# MiniBee.net
KiCad netlist of a schematic drawn in EAGLE
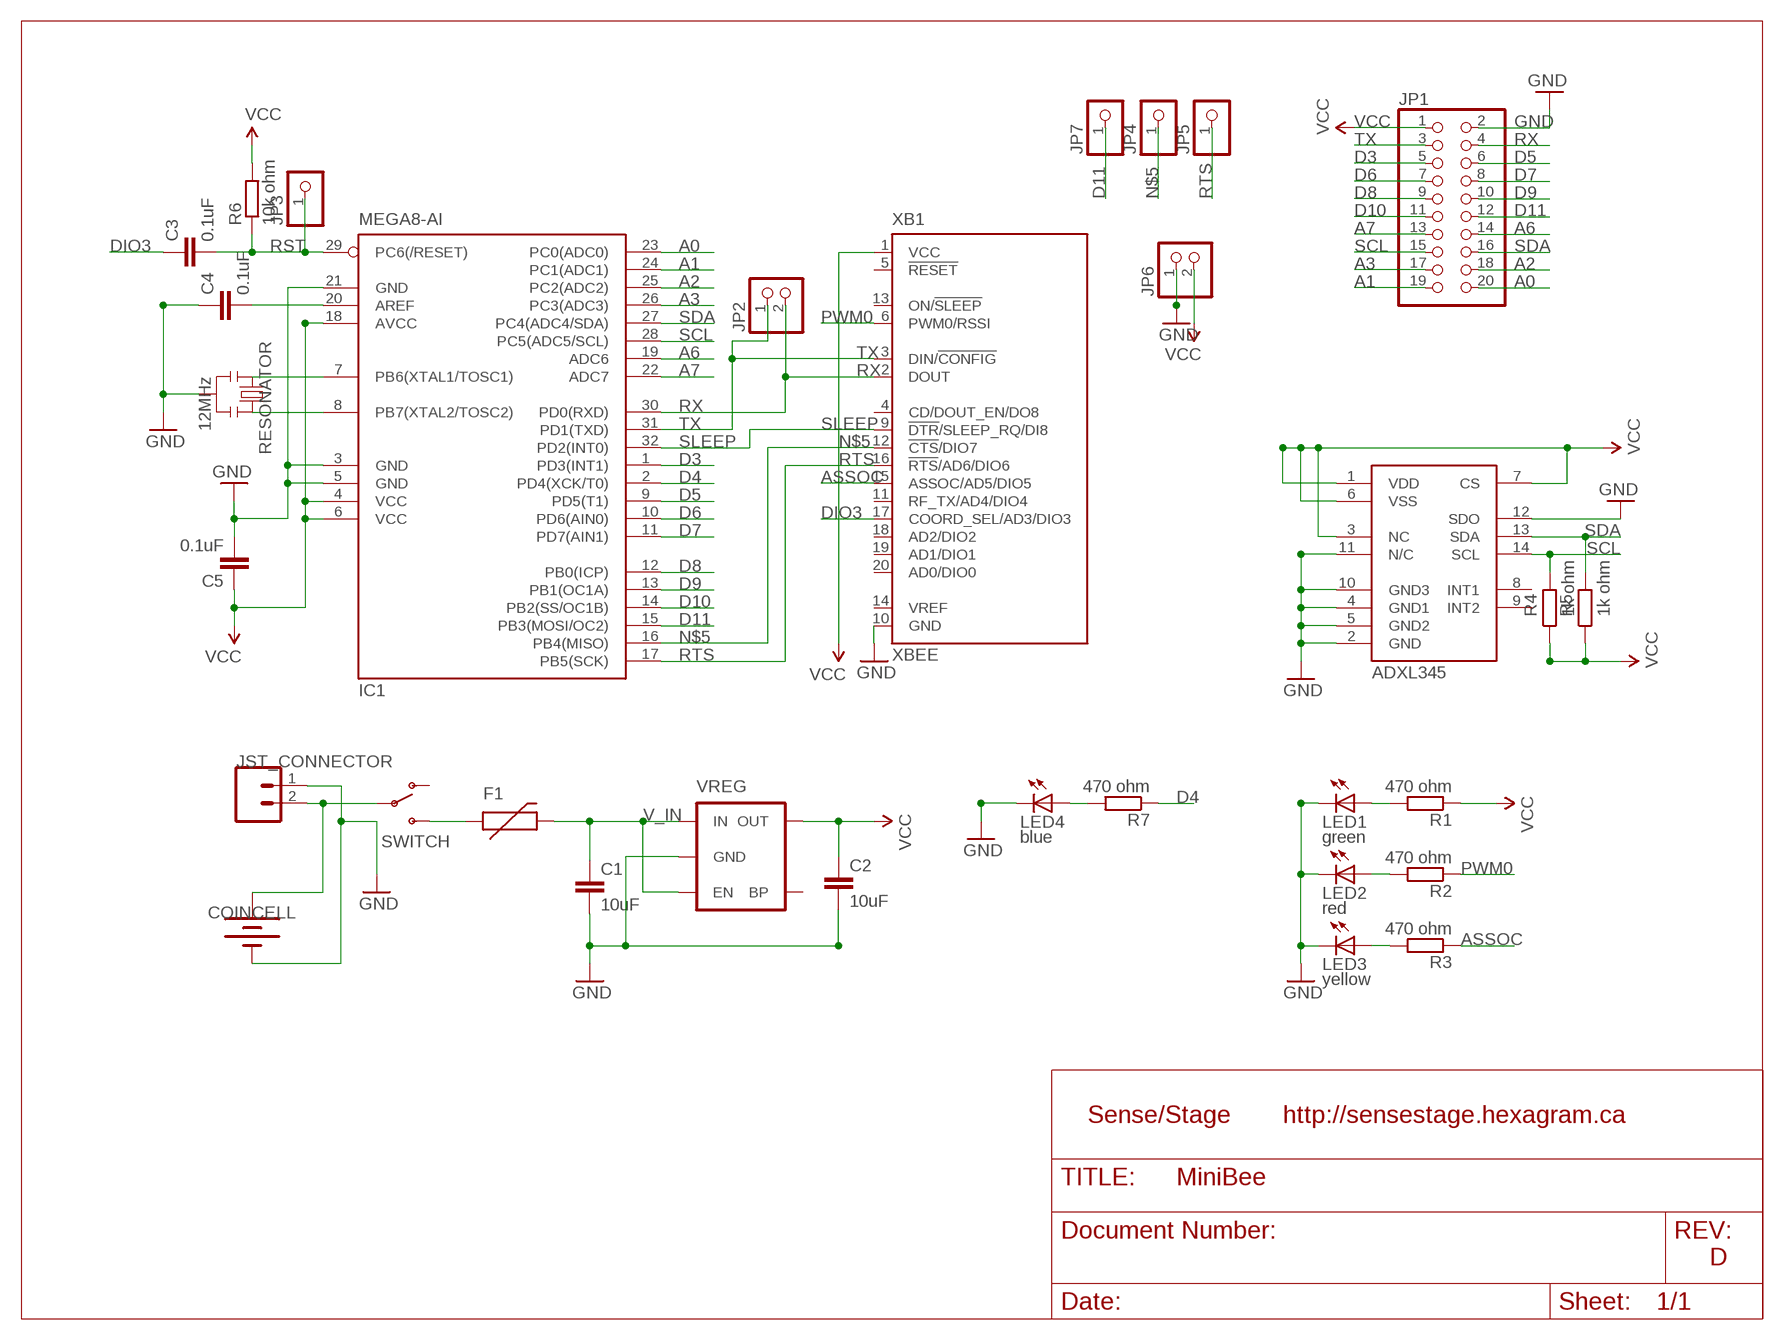
[diagram p0: schematic, sheet 1]

(export (version "E")
  (design (tool "Eeschema 10.0.6"))
  (components
    (comp (ref "C1")
      (value "10uF")
      (footprint "eagle-import:C0805")
      (libsource (lib "eagle-import") (part "C-EUC0805"))
    )
    (comp (ref "C2")
      (value "10uF")
      (footprint "eagle-import:C0805")
      (libsource (lib "eagle-import") (part "C-EUC0805"))
    )
    (comp (ref "C3")
      (value "0.1uF")
      (footprint "eagle-import:C0402")
      (libsource (lib "eagle-import") (part "C-EUC0402"))
    )
    (comp (ref "C4")
      (value "0.1uF")
      (footprint "eagle-import:C0402")
      (libsource (lib "eagle-import") (part "C-EUC0402"))
    )
    (comp (ref "C5")
      (value "0.1uF")
      (footprint "eagle-import:C0402K")
      (libsource (lib "eagle-import") (part "C-EUC0402K"))
    )
    (comp (ref "COINCELL")
      (value "COINCELL")
      (footprint "eagle-import:KEYSTONE_BATTERY_HOLDER")
      (libsource (lib "eagle-import") (part "KEYSTONE_BATTERY_HOLDER"))
    )
    (comp (ref "F1")
      (value "PTCSMD")
      (footprint "eagle-import:PTC-1206")
      (libsource (lib "eagle-import") (part "PTCSMD"))
    )
    (comp (ref "IC1")
      (value "MEGA8-AI")
      (footprint "eagle-import:TQFP32-08")
      (fields (field (name "MPN") "ATMEGA8-16AU"))
      (libsource (lib "eagle-import") (part "MEGA8-AI"))
    )
    (comp (ref "JP1")
      (value "PINHD-2X10")
      (footprint "eagle-import:2X10")
      (libsource (lib "eagle-import") (part "PINHD-2X10"))
    )
    (comp (ref "JP2")
      (value "PINHD-1X2")
      (footprint "eagle-import:1X02")
      (libsource (lib "eagle-import") (part "PINHD-1X2"))
    )
    (comp (ref "JP3")
      (value "PINHD-1X1")
      (footprint "eagle-import:1X01")
      (libsource (lib "eagle-import") (part "PINHD-1X1"))
    )
    (comp (ref "JP4")
      (value "PINHD-1X1")
      (footprint "eagle-import:1X01")
      (libsource (lib "eagle-import") (part "PINHD-1X1"))
    )
    (comp (ref "JP5")
      (value "PINHD-1X1")
      (footprint "eagle-import:1X01")
      (libsource (lib "eagle-import") (part "PINHD-1X1"))
    )
    (comp (ref "JP6")
      (value "PINHD-1X2")
      (footprint "eagle-import:1X02")
      (libsource (lib "eagle-import") (part "PINHD-1X2"))
    )
    (comp (ref "JP7")
      (value "PINHD-1X1")
      (footprint "eagle-import:1X01")
      (libsource (lib "eagle-import") (part "PINHD-1X1"))
    )
    (comp (ref "JST_CONNECTOR")
      (value "JST_CONNECTOR")
      (footprint "eagle-import:S2B-PH")
      (libsource (lib "eagle-import") (part "M02-JST-2MM-SMT"))
    )
    (comp (ref "LED1")
      (value "green")
      (footprint "eagle-import:CHIP-LED0603")
      (libsource (lib "eagle-import") (part "LEDCHIP-LED0603"))
    )
    (comp (ref "LED2")
      (value "red")
      (footprint "eagle-import:CHIP-LED0603")
      (libsource (lib "eagle-import") (part "LEDCHIP-LED0603"))
    )
    (comp (ref "LED3")
      (value "yellow")
      (footprint "eagle-import:CHIP-LED0603")
      (libsource (lib "eagle-import") (part "LEDCHIP-LED0603"))
    )
    (comp (ref "LED4")
      (value "blue")
      (footprint "eagle-import:CHIP-LED0603")
      (libsource (lib "eagle-import") (part "LEDCHIP-LED0603"))
    )
    (comp (ref "R1")
      (value "470 ohm")
      (footprint "eagle-import:R0402")
      (libsource (lib "eagle-import") (part "R-EU_R0402"))
    )
    (comp (ref "R2")
      (value "470 ohm")
      (footprint "eagle-import:R0402")
      (libsource (lib "eagle-import") (part "R-EU_R0402"))
    )
    (comp (ref "R3")
      (value "470 ohm")
      (footprint "eagle-import:R0402")
      (libsource (lib "eagle-import") (part "R-EU_R0402"))
    )
    (comp (ref "R4")
      (value "1k ohm")
      (footprint "eagle-import:R0402")
      (libsource (lib "eagle-import") (part "R-EU_R0402"))
    )
    (comp (ref "R5")
      (value "1k ohm")
      (footprint "eagle-import:R0402")
      (libsource (lib "eagle-import") (part "R-EU_R0402"))
    )
    (comp (ref "R6")
      (value "10k ohm")
      (footprint "eagle-import:R0402")
      (libsource (lib "eagle-import") (part "R-EU_R0402"))
    )
    (comp (ref "R7")
      (value "470 ohm")
      (footprint "eagle-import:R0402")
      (libsource (lib "eagle-import") (part "R-EU_R0402"))
    )
    (comp (ref "RESONATOR")
      (value "12MHz")
      (footprint "eagle-import:RESONATOR-SMD")
      (libsource (lib "eagle-import") (part "RESONATORSMD"))
    )
    (comp (ref "SWITCH")
      (value "MYSHIT_PCM_SWITCH")
      (footprint "eagle-import:MYSHIT_PCM_SWITCH_RA")
      (libsource (lib "eagle-import") (part "MYSHIT_PCM_SWITCH"))
    )
    (comp (ref "U1")
      (value "ADXL345")
      (footprint "eagle-import:LGA14")
      (libsource (lib "eagle-import") (part "ADXL345"))
    )
    (comp (ref "VREG")
      (value "V_REG_LDOSMD")
      (footprint "eagle-import:SOT23-5")
      (libsource (lib "eagle-import") (part "V_REG_LDOSMD"))
    )
    (comp (ref "XB1")
      (value "XBEE")
      (footprint "eagle-import:XBEE")
      (fields (field (name "MPN") "XBP24-Z7UIT-004"))
      (libsource (lib "eagle-import") (part "XBEE"))
    )
  )
  (nets
    (net (code "1") (name "/A0") (class "Default")
      (node (ref "IC1") (pin "23") (pinfunction "PC0(ADC0)_23") (pintype "bidirectional"))
      (node (ref "JP1") (pin "20") (pinfunction "20_20") (pintype "passive"))
    )
    (net (code "2") (name "/A1") (class "Default")
      (node (ref "IC1") (pin "24") (pinfunction "PC1(ADC1)_24") (pintype "bidirectional"))
      (node (ref "JP1") (pin "19") (pinfunction "19_19") (pintype "passive"))
    )
    (net (code "3") (name "/A2") (class "Default")
      (node (ref "IC1") (pin "25") (pinfunction "PC2(ADC2)_25") (pintype "bidirectional"))
      (node (ref "JP1") (pin "18") (pinfunction "18_18") (pintype "passive"))
    )
    (net (code "4") (name "/A3") (class "Default")
      (node (ref "IC1") (pin "26") (pinfunction "PC3(ADC3)_26") (pintype "bidirectional"))
      (node (ref "JP1") (pin "17") (pinfunction "17_17") (pintype "passive"))
    )
    (net (code "5") (name "/A6") (class "Default")
      (node (ref "IC1") (pin "19") (pinfunction "ADC6_19") (pintype "bidirectional"))
      (node (ref "JP1") (pin "14") (pinfunction "14_14") (pintype "passive"))
    )
    (net (code "6") (name "/A7") (class "Default")
      (node (ref "IC1") (pin "22") (pinfunction "ADC7_22") (pintype "bidirectional"))
      (node (ref "JP1") (pin "13") (pinfunction "13_13") (pintype "passive"))
    )
    (net (code "7") (name "/ASSOC") (class "Default")
      (node (ref "R3") (pin "1") (pinfunction "1_1") (pintype "passive"))
      (node (ref "XB1") (pin "15") (pinfunction "ASSOC/AD5/DIO5_15") (pintype "bidirectional"))
    )
    (net (code "8") (name "/D3") (class "Default")
      (node (ref "IC1") (pin "1") (pinfunction "PD3(INT1)_1") (pintype "bidirectional"))
      (node (ref "JP1") (pin "5") (pinfunction "5_5") (pintype "passive"))
    )
    (net (code "9") (name "/D4") (class "Default")
      (node (ref "IC1") (pin "2") (pinfunction "PD4(XCK/T0)_2") (pintype "bidirectional"))
      (node (ref "R7") (pin "1") (pinfunction "1_1") (pintype "passive"))
    )
    (net (code "10") (name "/D5") (class "Default")
      (node (ref "IC1") (pin "9") (pinfunction "PD5(T1)_9") (pintype "bidirectional"))
      (node (ref "JP1") (pin "6") (pinfunction "6_6") (pintype "passive"))
    )
    (net (code "11") (name "/D6") (class "Default")
      (node (ref "IC1") (pin "10") (pinfunction "PD6(AIN0)_10") (pintype "bidirectional"))
      (node (ref "JP1") (pin "7") (pinfunction "7_7") (pintype "passive"))
    )
    (net (code "12") (name "/D7") (class "Default")
      (node (ref "IC1") (pin "11") (pinfunction "PD7(AIN1)_11") (pintype "bidirectional"))
      (node (ref "JP1") (pin "8") (pinfunction "8_8") (pintype "passive"))
    )
    (net (code "13") (name "/D8") (class "Default")
      (node (ref "IC1") (pin "12") (pinfunction "PB0(ICP)_12") (pintype "bidirectional"))
      (node (ref "JP1") (pin "9") (pinfunction "9_9") (pintype "passive"))
    )
    (net (code "14") (name "/D9") (class "Default")
      (node (ref "IC1") (pin "13") (pinfunction "PB1(OC1A)_13") (pintype "bidirectional"))
      (node (ref "JP1") (pin "10") (pinfunction "10_10") (pintype "passive"))
    )
    (net (code "15") (name "/D10") (class "Default")
      (node (ref "IC1") (pin "14") (pinfunction "PB2(SS/OC1B)_14") (pintype "bidirectional"))
      (node (ref "JP1") (pin "11") (pinfunction "11_11") (pintype "passive"))
    )
    (net (code "16") (name "/D11") (class "Default")
      (node (ref "IC1") (pin "15") (pinfunction "PB3(MOSI/OC2)_15") (pintype "bidirectional"))
      (node (ref "JP1") (pin "12") (pinfunction "12_12") (pintype "passive"))
      (node (ref "JP7") (pin "1") (pinfunction "1_1") (pintype "passive"))
    )
    (net (code "17") (name "/DIO3") (class "Default")
      (node (ref "C3") (pin "1") (pinfunction "1_1") (pintype "passive"))
      (node (ref "XB1") (pin "17") (pinfunction "COORD_SEL/AD3/DIO3_17") (pintype "bidirectional"))
    )
    (net (code "18") (name "/N$5") (class "Default")
      (node (ref "IC1") (pin "16") (pinfunction "PB4(MISO)_16") (pintype "bidirectional"))
      (node (ref "JP4") (pin "1") (pinfunction "1_1") (pintype "passive"))
      (node (ref "XB1") (pin "12") (pinfunction "~{CTS}/DIO7_12") (pintype "bidirectional"))
    )
    (net (code "19") (name "/PWM0") (class "Default")
      (node (ref "R2") (pin "1") (pinfunction "1_1") (pintype "passive"))
      (node (ref "XB1") (pin "6") (pinfunction "PWM0/RSSI_6") (pintype "output"))
    )
    (net (code "20") (name "/RST") (class "Default")
      (node (ref "C3") (pin "2") (pinfunction "2_2") (pintype "passive"))
      (node (ref "IC1") (pin "29") (pinfunction "PC6(/RESET)_29") (pintype "bidirectional"))
      (node (ref "JP3") (pin "1") (pinfunction "1_1") (pintype "passive"))
      (node (ref "R6") (pin "1") (pinfunction "1_1") (pintype "passive"))
    )
    (net (code "21") (name "/RTS") (class "Default")
      (node (ref "IC1") (pin "17") (pinfunction "PB5(SCK)_17") (pintype "bidirectional"))
      (node (ref "JP5") (pin "1") (pinfunction "1_1") (pintype "passive"))
      (node (ref "XB1") (pin "16") (pinfunction "~{RTS}/AD6/DIO6_16") (pintype "bidirectional"))
    )
    (net (code "22") (name "/RX") (class "Default")
      (node (ref "IC1") (pin "30") (pinfunction "PD0(RXD)_30") (pintype "bidirectional"))
      (node (ref "JP1") (pin "4") (pinfunction "4_4") (pintype "passive"))
      (node (ref "JP2") (pin "2") (pinfunction "2_2") (pintype "passive"))
      (node (ref "XB1") (pin "2") (pinfunction "DOUT_2") (pintype "output"))
    )
    (net (code "23") (name "/SCL") (class "Default")
      (node (ref "IC1") (pin "28") (pinfunction "PC5(ADC5/SCL)_28") (pintype "bidirectional"))
      (node (ref "JP1") (pin "15") (pinfunction "15_15") (pintype "passive"))
      (node (ref "R4") (pin "2") (pinfunction "2_2") (pintype "passive"))
      (node (ref "U1") (pin "14") (pinfunction "SCL_14") (pintype "bidirectional"))
    )
    (net (code "24") (name "/SDA") (class "Default")
      (node (ref "IC1") (pin "27") (pinfunction "PC4(ADC4/SDA)_27") (pintype "bidirectional"))
      (node (ref "JP1") (pin "16") (pinfunction "16_16") (pintype "passive"))
      (node (ref "R5") (pin "2") (pinfunction "2_2") (pintype "passive"))
      (node (ref "U1") (pin "13") (pinfunction "SDA_13") (pintype "bidirectional"))
    )
    (net (code "25") (name "/SLEEP") (class "Default")
      (node (ref "IC1") (pin "32") (pinfunction "PD2(INT0)_32") (pintype "bidirectional"))
      (node (ref "XB1") (pin "9") (pinfunction "~{DTR}/SLEEP_RQ/DI8_9") (pintype "bidirectional"))
    )
    (net (code "26") (name "/TX") (class "Default")
      (node (ref "IC1") (pin "31") (pinfunction "PD1(TXD)_31") (pintype "bidirectional"))
      (node (ref "JP1") (pin "3") (pinfunction "3_3") (pintype "passive"))
      (node (ref "JP2") (pin "1") (pinfunction "1_1") (pintype "passive"))
      (node (ref "XB1") (pin "3") (pinfunction "DIN/~{CONFIG}_3") (pintype "input"))
    )
    (net (code "27") (name "/V_IN") (class "Default")
      (node (ref "C1") (pin "1") (pinfunction "1_1") (pintype "passive"))
      (node (ref "F1") (pin "2") (pinfunction "2_2") (pintype "bidirectional"))
      (node (ref "VREG") (pin "1") (pinfunction "IN_1") (pintype "input"))
      (node (ref "VREG") (pin "3") (pinfunction "EN_3") (pintype "input"))
    )
    (net (code "28") (name "GND") (class "Default")
      (node (ref "C1") (pin "2") (pinfunction "2_2") (pintype "passive"))
      (node (ref "C2") (pin "2") (pinfunction "2_2") (pintype "passive"))
      (node (ref "C4") (pin "1") (pinfunction "1_1") (pintype "passive"))
      (node (ref "C5") (pin "2") (pinfunction "2_2") (pintype "passive"))
      (node (ref "COINCELL") (pin "-") (pinfunction "-_-") (pintype "power_in"))
      (node (ref "IC1") (pin "21") (pinfunction "GND_21") (pintype "power_in"))
      (node (ref "IC1") (pin "3") (pinfunction "GND_3") (pintype "power_in"))
      (node (ref "IC1") (pin "5") (pinfunction "GND_5") (pintype "power_in"))
      (node (ref "JP1") (pin "2") (pinfunction "2_2") (pintype "passive"))
      (node (ref "JP6") (pin "1") (pinfunction "1_1") (pintype "passive"))
      (node (ref "JST_CONNECTOR") (pin "1") (pinfunction "1_1") (pintype "passive"))
      (node (ref "LED1") (pin "C") (pinfunction "C_C") (pintype "passive"))
      (node (ref "LED2") (pin "C") (pinfunction "C_C") (pintype "passive"))
      (node (ref "LED3") (pin "C") (pinfunction "C_C") (pintype "passive"))
      (node (ref "LED4") (pin "C") (pinfunction "C_C") (pintype "passive"))
      (node (ref "RESONATOR") (pin "2") (pinfunction "2_2") (pintype "passive"))
      (node (ref "U1") (pin "10") (pinfunction "GND3_10") (pintype "bidirectional"))
      (node (ref "U1") (pin "11") (pinfunction "N/C_11") (pintype "bidirectional"))
      (node (ref "U1") (pin "12") (pinfunction "SDO_12") (pintype "bidirectional"))
      (node (ref "U1") (pin "2") (pinfunction "GND_2") (pintype "bidirectional"))
      (node (ref "U1") (pin "4") (pinfunction "GND1_4") (pintype "bidirectional"))
      (node (ref "U1") (pin "5") (pinfunction "GND2_5") (pintype "bidirectional"))
      (node (ref "VREG") (pin "2") (pinfunction "GND_2") (pintype "input"))
      (node (ref "XB1") (pin "10") (pinfunction "GND_10") (pintype "power_in"))
    )
    (net (code "29") (name "Net-(IC1-AREF)") (class "Default")
      (node (ref "C4") (pin "2") (pinfunction "2_2") (pintype "passive"))
      (node (ref "IC1") (pin "20") (pinfunction "AREF_20") (pintype "passive"))
    )
    (net (code "30") (name "Net-(IC1-PB6(XTAL1{slash}TOSC1))") (class "Default")
      (node (ref "IC1") (pin "7") (pinfunction "PB6(XTAL1/TOSC1)_7") (pintype "bidirectional"))
      (node (ref "RESONATOR") (pin "1") (pinfunction "1_1") (pintype "passive"))
    )
    (net (code "31") (name "Net-(IC1-PB7(XTAL2{slash}TOSC2))") (class "Default")
      (node (ref "IC1") (pin "8") (pinfunction "PB7(XTAL2/TOSC2)_8") (pintype "bidirectional"))
      (node (ref "RESONATOR") (pin "3") (pinfunction "3_3") (pintype "passive"))
    )
    (net (code "32") (name "Net-(LED1-PadA)") (class "Default")
      (node (ref "LED1") (pin "A") (pinfunction "A_A") (pintype "passive"))
      (node (ref "R1") (pin "2") (pinfunction "2_2") (pintype "passive"))
    )
    (net (code "33") (name "Net-(LED2-PadA)") (class "Default")
      (node (ref "LED2") (pin "A") (pinfunction "A_A") (pintype "passive"))
      (node (ref "R2") (pin "2") (pinfunction "2_2") (pintype "passive"))
    )
    (net (code "34") (name "Net-(LED3-PadA)") (class "Default")
      (node (ref "LED3") (pin "A") (pinfunction "A_A") (pintype "passive"))
      (node (ref "R3") (pin "2") (pinfunction "2_2") (pintype "passive"))
    )
    (net (code "35") (name "Net-(LED4-PadA)") (class "Default")
      (node (ref "LED4") (pin "A") (pinfunction "A_A") (pintype "passive"))
      (node (ref "R7") (pin "2") (pinfunction "2_2") (pintype "passive"))
    )
    (net (code "36") (name "Net-(SWITCH-P)") (class "Default")
      (node (ref "COINCELL") (pin "+") (pinfunction "+_+") (pintype "power_in"))
      (node (ref "JST_CONNECTOR") (pin "2") (pinfunction "2_2") (pintype "passive"))
      (node (ref "SWITCH") (pin "2") (pinfunction "P_2") (pintype "passive"))
    )
    (net (code "37") (name "Net-(SWITCH-S)") (class "Default")
      (node (ref "F1") (pin "1") (pinfunction "1_1") (pintype "bidirectional"))
      (node (ref "SWITCH") (pin "3") (pinfunction "S_3") (pintype "passive"))
    )
    (net (code "38") (name "VCC") (class "Default")
      (node (ref "C2") (pin "1") (pinfunction "1_1") (pintype "passive"))
      (node (ref "C5") (pin "1") (pinfunction "1_1") (pintype "passive"))
      (node (ref "IC1") (pin "18") (pinfunction "AVCC_18") (pintype "power_in"))
      (node (ref "IC1") (pin "4") (pinfunction "VCC_4") (pintype "power_in"))
      (node (ref "IC1") (pin "6") (pinfunction "VCC_6") (pintype "power_in"))
      (node (ref "JP1") (pin "1") (pinfunction "1_1") (pintype "passive"))
      (node (ref "JP6") (pin "2") (pinfunction "2_2") (pintype "passive"))
      (node (ref "R1") (pin "1") (pinfunction "1_1") (pintype "passive"))
      (node (ref "R4") (pin "1") (pinfunction "1_1") (pintype "passive"))
      (node (ref "R5") (pin "1") (pinfunction "1_1") (pintype "passive"))
      (node (ref "R6") (pin "2") (pinfunction "2_2") (pintype "passive"))
      (node (ref "U1") (pin "1") (pinfunction "VDD_1") (pintype "bidirectional"))
      (node (ref "U1") (pin "3") (pinfunction "NC_3") (pintype "bidirectional"))
      (node (ref "U1") (pin "6") (pinfunction "VSS_6") (pintype "bidirectional"))
      (node (ref "U1") (pin "7") (pinfunction "CS_7") (pintype "bidirectional"))
      (node (ref "VREG") (pin "5") (pinfunction "OUT_5") (pintype "passive"))
      (node (ref "XB1") (pin "1") (pinfunction "VCC_1") (pintype "power_in"))
    )
    (net (code "39") (name "unconnected-(SWITCH-O-Pad1)") (class "Default")
      (node (ref "SWITCH") (pin "1") (pinfunction "O_1") (pintype "passive"))
    )
    (net (code "40") (name "unconnected-(U1-INT1-Pad8)") (class "Default")
      (node (ref "U1") (pin "8") (pinfunction "INT1_8") (pintype "bidirectional"))
    )
    (net (code "41") (name "unconnected-(U1-INT2-Pad9)") (class "Default")
      (node (ref "U1") (pin "9") (pinfunction "INT2_9") (pintype "bidirectional"))
    )
    (net (code "42") (name "unconnected-(VREG-BP-Pad4)") (class "Default")
      (node (ref "VREG") (pin "4") (pinfunction "BP_4") (pintype "input"))
    )
    (net (code "43") (name "unconnected-(XB1-AD0{slash}DIO0-Pad20)") (class "Default")
      (node (ref "XB1") (pin "20") (pinfunction "AD0/DIO0_20") (pintype "bidirectional"))
    )
    (net (code "44") (name "unconnected-(XB1-AD1{slash}DIO1-Pad19)") (class "Default")
      (node (ref "XB1") (pin "19") (pinfunction "AD1/DIO1_19") (pintype "bidirectional"))
    )
    (net (code "45") (name "unconnected-(XB1-AD2{slash}DIO2-Pad18)") (class "Default")
      (node (ref "XB1") (pin "18") (pinfunction "AD2/DIO2_18") (pintype "bidirectional"))
    )
    (net (code "46") (name "unconnected-(XB1-CD{slash}DOUT_EN{slash}DO8-Pad4)") (class "Default")
      (node (ref "XB1") (pin "4") (pinfunction "CD/DOUT_EN/DO8_4") (pintype "output"))
    )
    (net (code "47") (name "unconnected-(XB1-ON{slash}~{SLEEP}-Pad13)") (class "Default")
      (node (ref "XB1") (pin "13") (pinfunction "ON/~{SLEEP}_13") (pintype "output"))
    )
    (net (code "48") (name "unconnected-(XB1-RF_TX{slash}AD4{slash}DIO4-Pad11)") (class "Default")
      (node (ref "XB1") (pin "11") (pinfunction "RF_TX/AD4/DIO4_11") (pintype "bidirectional"))
    )
    (net (code "49") (name "unconnected-(XB1-VREF-Pad14)") (class "Default")
      (node (ref "XB1") (pin "14") (pinfunction "VREF_14") (pintype "input"))
    )
    (net (code "50") (name "unconnected-(XB1-~{RESET}-Pad5)") (class "Default")
      (node (ref "XB1") (pin "5") (pinfunction "~{RESET}_5") (pintype "input"))
    )
  )
)
